# obc_rtc.net
KiCad netlist of a schematic drawn in Altium Designer
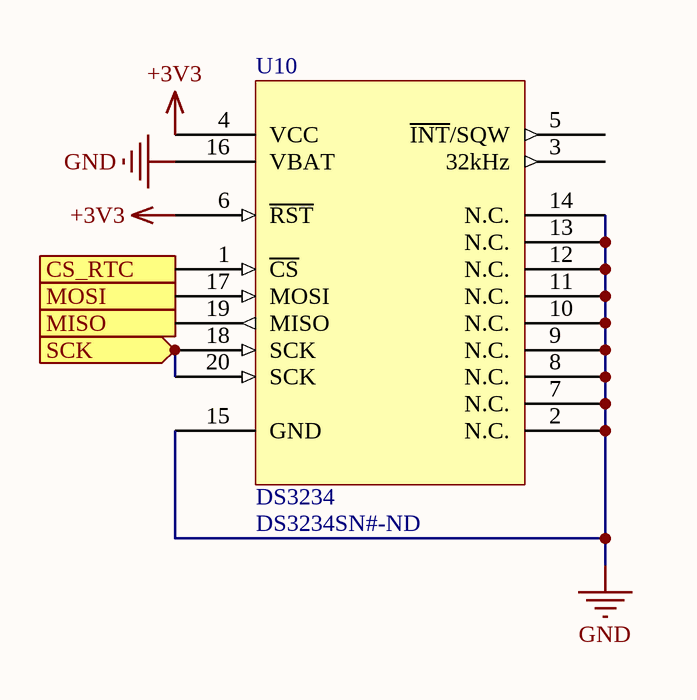
[diagram p0: obc_rtc.SchDoc]

(export (version "E")
  (design (tool "Eeschema 10.0.6"))
  (components
    (comp (ref "U10")
      (value "DS3234")
      (footprint "SOIC127P1032X265-20N")
      (description "SPI bus RTC with integrated crystal and SRAM")
      (fields (field (name "SUPPLIER PART NUMBER 1") "DS3234SN#-ND"))
      (libsource (lib "heron-general") (part "DS3234"))
    )
  )
  (nets
    (net (code "1") (name "+3V3") (class "Default")
      (node (ref "U10") (pin "4") (pinfunction "VCC_4") (pintype "power_in"))
      (node (ref "U10") (pin "6") (pinfunction "~{RST}_6") (pintype "input"))
    )
    (net (code "2") (name "/CS_RTC") (class "Default")
      (node (ref "U10") (pin "1") (pinfunction "~{CS}_1") (pintype "input"))
    )
    (net (code "3") (name "/MISO") (class "Default")
      (node (ref "U10") (pin "19") (pinfunction "MISO_19") (pintype "output"))
    )
    (net (code "4") (name "/MOSI") (class "Default")
      (node (ref "U10") (pin "17") (pinfunction "MOSI_17") (pintype "input"))
    )
    (net (code "5") (name "/SCK") (class "Default")
      (node (ref "U10") (pin "18") (pinfunction "SCK_18") (pintype "input"))
      (node (ref "U10") (pin "20") (pinfunction "SCK_20") (pintype "input"))
    )
    (net (code "6") (name "GND") (class "Default")
      (node (ref "U10") (pin "10") (pinfunction "N.C._10") (pintype "passive"))
      (node (ref "U10") (pin "11") (pinfunction "N.C._11") (pintype "passive"))
      (node (ref "U10") (pin "12") (pinfunction "N.C._12") (pintype "passive"))
      (node (ref "U10") (pin "13") (pinfunction "N.C._13") (pintype "passive"))
      (node (ref "U10") (pin "14") (pinfunction "N.C._14") (pintype "passive"))
      (node (ref "U10") (pin "15") (pinfunction "GND_15") (pintype "power_in"))
      (node (ref "U10") (pin "16") (pinfunction "VBAT_16") (pintype "power_in"))
      (node (ref "U10") (pin "2") (pinfunction "N.C._2") (pintype "passive"))
      (node (ref "U10") (pin "7") (pinfunction "N.C._7") (pintype "passive"))
      (node (ref "U10") (pin "8") (pinfunction "N.C._8") (pintype "passive"))
      (node (ref "U10") (pin "9") (pinfunction "N.C._9") (pintype "passive"))
    )
    (net (code "7") (name "unconnected-(U10-32kHz-Pad3)") (class "Default")
      (node (ref "U10") (pin "3") (pinfunction "32kHz_3") (pintype "output"))
    )
    (net (code "8") (name "unconnected-(U10-~{INT}{slash}SQW-Pad5)") (class "Default")
      (node (ref "U10") (pin "5") (pinfunction "~{INT}/SQW_5") (pintype "output"))
    )
  )
)
